# 3_0V_2_5V_DIST.net
KiCad netlist of a schematic drawn in Altium Designer
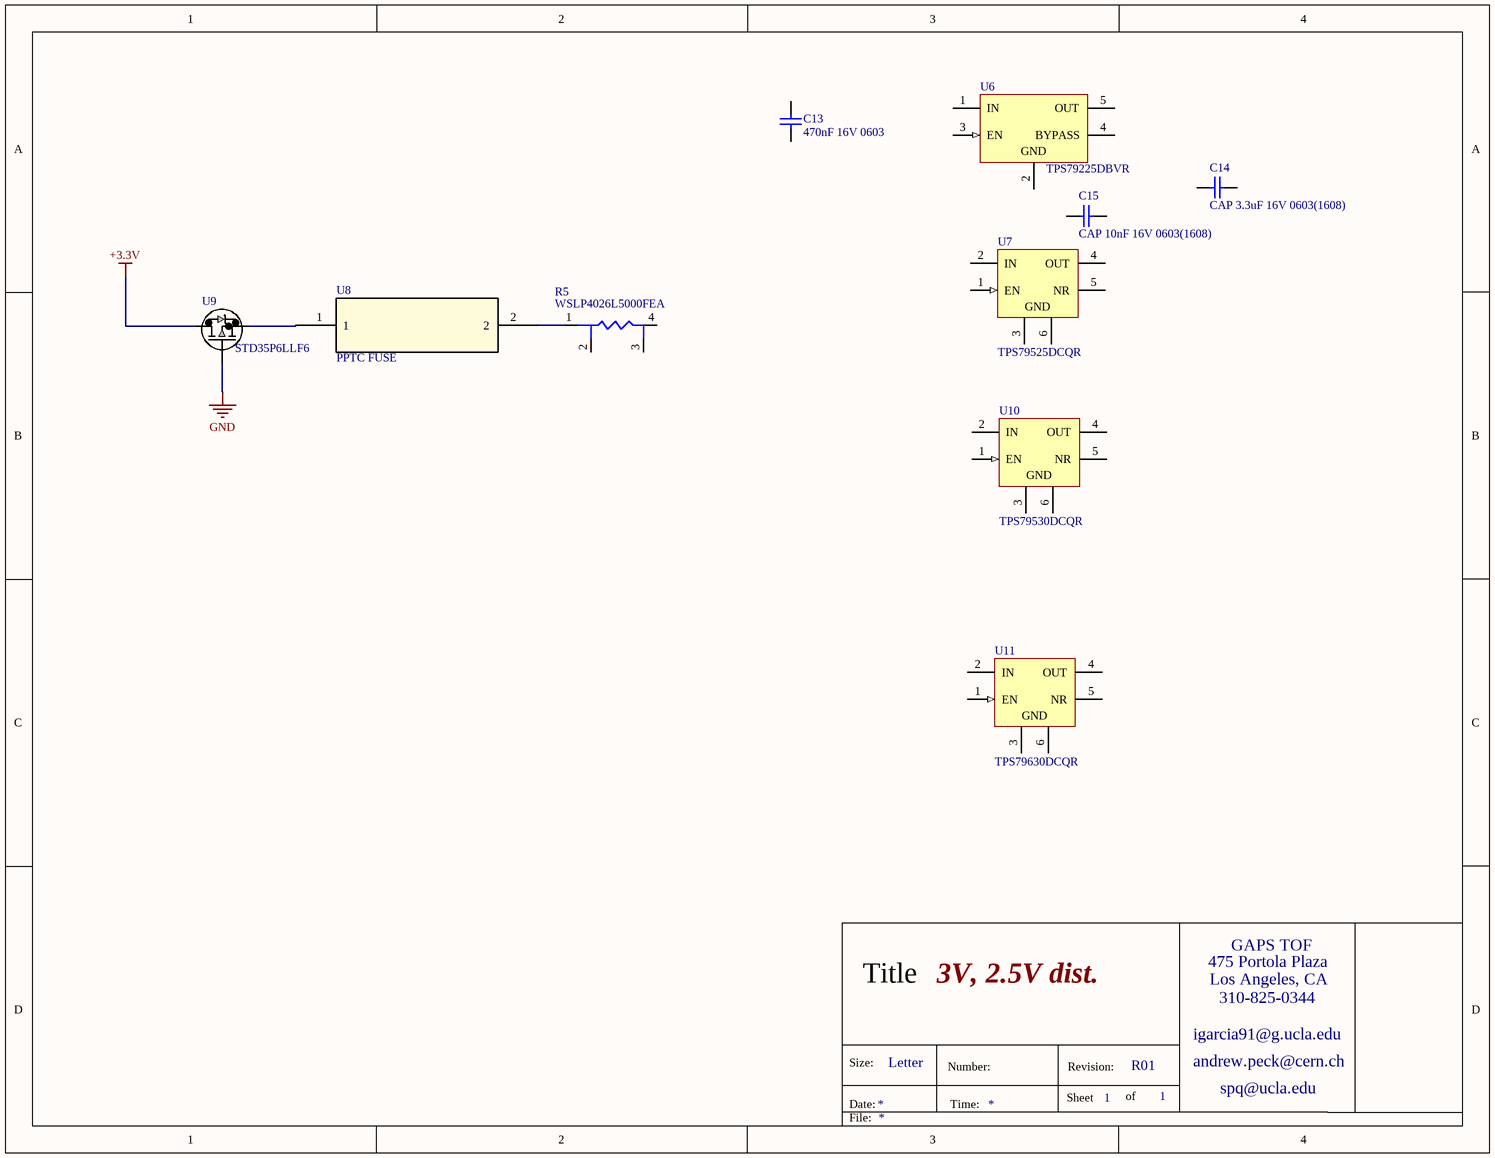
[diagram p0: 3_0V_2_5V_DIST.SchDoc]

(export (version "E")
  (design (tool "Eeschema 10.0.6"))
  (components
    (comp (ref "C13")
      (value "470nF 16V 0603")
      (footprint "CAPC0603(1608)100_M")
      (description "CAP 470nF 16V ±10% 0603 (1608 Metric) Thickness 1mm SMD")
      (fields (field (name "TOLERANCE") "Â±10%"))
      (libsource (lib "Altium Content Vault") (part "CAP"))
    )
    (comp (ref "C14")
      (value "CAP 3.3uF 16V 0603(1608)")
      (footprint "CAPC0603(1608)100_L")
      (description "CAP 3.3uF 16V ±20% 0603 (1608 Metric) Thickness 1mm SMD")
      (fields (field (name "TOLERANCE") "Â±20%"))
      (libsource (lib "Altium Content Vault") (part "CAP"))
    )
    (comp (ref "C15")
      (value "CAP 10nF 16V 0603(1608)")
      (footprint "CAPC0603(1608)100_L")
      (description "CAP 10nF 16V ±10% 0603 (1608 Metric) Thickness 1mm SMD")
      (fields (field (name "TOLERANCE") "Â±10%"))
      (libsource (lib "Altium Content Vault") (part "CAP"))
    )
    (comp (ref "R5")
      (value "WSLP4026L5000FEA")
      (description "Current Sense Resistors - SMD 7watt .0005ohm 1%")
      (libsource (lib "WSLP4026L5000FEA") (part "WSLP4026L5000FEA"))
    )
    (comp (ref "U6")
      (value "TPS79225DBVR")
      (footprint "DBV0005A_M")
      (fields (field (name "MANUFACTURER") "Texas Instruments"))
      (libsource (lib "TPS79225DBVR") (part "CMP-0394-00239-2"))
    )
    (comp (ref "U7")
      (value "TPS79525DCQR")
      (footprint "DCQ0006A_L")
      (fields (field (name "MANUFACTURER") "Texas Instruments"))
      (libsource (lib "TPS79525DCQR") (part "CMP-0395-00444-2"))
    )
    (comp (ref "U8")
      (value "PPTC FUSE")
      (footprint "0ZCF")
      (description "Resettable Fuses - PPTC")
      (fields (field (name "MANUFACTURER_PART_NUMBER") "0ZCF0250FF2C"))
      (libsource (lib "0ZCF0250FF2C") (part "0ZCF0250FF2C"))
    )
    (comp (ref "U9")
      (value "STD35P6LLF6")
      (footprint "DPAK")
      (description "MOSFET P-channel 60 V, 0.025 Ohm typ., 35 A STripFET F6 Power MOSFET in a DPAK package")
      (fields (field (name "MANUFACTURER_PART_NUMBER") "STD35NF06T4"))
      (libsource (lib "STD35P6LLF6") (part "STD35P6LLF6"))
    )
    (comp (ref "U10")
      (value "TPS79530DCQR")
      (footprint "DCQ0006A_L")
      (fields (field (name "MANUFACTURER") "Texas Instruments"))
      (libsource (lib "TPS79530DCQR") (part "CMP-0395-00302-2"))
    )
    (comp (ref "U11")
      (value "TPS79630DCQR")
      (footprint "DCQ0006A_L")
      (fields (field (name "MANUFACTURER") "Texas Instruments"))
      (libsource (lib "TPS79630DCQR") (part "CMP-0395-00336-2"))
    )
  )
  (nets
    (net (code "1") (name "+3.3V") (class "Default")
      (node (ref "U9") (pin "2") (pinfunction "D_2") (pintype "passive"))
    )
    (net (code "2") (name "GND") (class "Default")
      (node (ref "U9") (pin "1") (pinfunction "G_1") (pintype "passive"))
    )
    (net (code "3") (name "Net-(R5-Pad1)") (class "Default")
      (node (ref "R5") (pin "1") (pintype "passive"))
      (node (ref "U8") (pin "2") (pinfunction "2_2") (pintype "passive"))
    )
    (net (code "4") (name "Net-(U9-S)") (class "Default")
      (node (ref "U8") (pin "1") (pinfunction "1_1") (pintype "passive"))
      (node (ref "U9") (pin "3") (pinfunction "S_3") (pintype "passive"))
    )
    (net (code "5") (name "unconnected-(C13-Pad1)") (class "Default")
      (node (ref "C13") (pin "1") (pinfunction "1_1") (pintype "passive"))
    )
    (net (code "6") (name "unconnected-(C13-Pad2)") (class "Default")
      (node (ref "C13") (pin "2") (pinfunction "2_2") (pintype "passive"))
    )
    (net (code "7") (name "unconnected-(C14-Pad1)") (class "Default")
      (node (ref "C14") (pin "1") (pinfunction "1_1") (pintype "passive"))
    )
    (net (code "8") (name "unconnected-(C14-Pad2)") (class "Default")
      (node (ref "C14") (pin "2") (pinfunction "2_2") (pintype "passive"))
    )
    (net (code "9") (name "unconnected-(C15-Pad1)") (class "Default")
      (node (ref "C15") (pin "1") (pinfunction "1_1") (pintype "passive"))
    )
    (net (code "10") (name "unconnected-(C15-Pad2)") (class "Default")
      (node (ref "C15") (pin "2") (pinfunction "2_2") (pintype "passive"))
    )
    (net (code "11") (name "unconnected-(R5-Pad2)") (class "Default")
      (node (ref "R5") (pin "2") (pintype "passive"))
    )
    (net (code "12") (name "unconnected-(R5-Pad3)") (class "Default")
      (node (ref "R5") (pin "3") (pintype "passive"))
    )
    (net (code "13") (name "unconnected-(R5-Pad4)") (class "Default")
      (node (ref "R5") (pin "4") (pintype "passive"))
    )
    (net (code "14") (name "unconnected-(U6-BYPASS-Pad4)") (class "Default")
      (node (ref "U6") (pin "4") (pinfunction "BYPASS_4") (pintype "passive"))
    )
    (net (code "15") (name "unconnected-(U6-EN-Pad3)") (class "Default")
      (node (ref "U6") (pin "3") (pinfunction "EN_3") (pintype "input"))
    )
    (net (code "16") (name "unconnected-(U6-GND-Pad2)") (class "Default")
      (node (ref "U6") (pin "2") (pinfunction "GND_2") (pintype "power_in"))
    )
    (net (code "17") (name "unconnected-(U6-IN-Pad1)") (class "Default")
      (node (ref "U6") (pin "1") (pinfunction "IN_1") (pintype "power_in"))
    )
    (net (code "18") (name "unconnected-(U6-OUT-Pad5)") (class "Default")
      (node (ref "U6") (pin "5") (pinfunction "OUT_5") (pintype "power_in"))
    )
    (net (code "19") (name "unconnected-(U7-EN-Pad1)") (class "Default")
      (node (ref "U7") (pin "1") (pinfunction "EN_1") (pintype "input"))
    )
    (net (code "20") (name "unconnected-(U7-GND-Pad3)") (class "Default")
      (node (ref "U7") (pin "3") (pinfunction "GND_3") (pintype "power_in"))
    )
    (net (code "21") (name "unconnected-(U7-GND-Pad6)") (class "Default")
      (node (ref "U7") (pin "6") (pinfunction "GND_6") (pintype "power_in"))
    )
    (net (code "22") (name "unconnected-(U7-IN-Pad2)") (class "Default")
      (node (ref "U7") (pin "2") (pinfunction "IN_2") (pintype "power_in"))
    )
    (net (code "23") (name "unconnected-(U7-NR-Pad5)") (class "Default")
      (node (ref "U7") (pin "5") (pinfunction "NR_5") (pintype "passive"))
    )
    (net (code "24") (name "unconnected-(U7-OUT-Pad4)") (class "Default")
      (node (ref "U7") (pin "4") (pinfunction "OUT_4") (pintype "power_in"))
    )
    (net (code "25") (name "unconnected-(U10-EN-Pad1)") (class "Default")
      (node (ref "U10") (pin "1") (pinfunction "EN_1") (pintype "input"))
    )
    (net (code "26") (name "unconnected-(U10-GND-Pad3)") (class "Default")
      (node (ref "U10") (pin "3") (pinfunction "GND_3") (pintype "power_in"))
    )
    (net (code "27") (name "unconnected-(U10-GND-Pad6)") (class "Default")
      (node (ref "U10") (pin "6") (pinfunction "GND_6") (pintype "power_in"))
    )
    (net (code "28") (name "unconnected-(U10-IN-Pad2)") (class "Default")
      (node (ref "U10") (pin "2") (pinfunction "IN_2") (pintype "power_in"))
    )
    (net (code "29") (name "unconnected-(U10-NR-Pad5)") (class "Default")
      (node (ref "U10") (pin "5") (pinfunction "NR_5") (pintype "passive"))
    )
    (net (code "30") (name "unconnected-(U10-OUT-Pad4)") (class "Default")
      (node (ref "U10") (pin "4") (pinfunction "OUT_4") (pintype "power_in"))
    )
    (net (code "31") (name "unconnected-(U11-EN-Pad1)") (class "Default")
      (node (ref "U11") (pin "1") (pinfunction "EN_1") (pintype "input"))
    )
    (net (code "32") (name "unconnected-(U11-GND-Pad3)") (class "Default")
      (node (ref "U11") (pin "3") (pinfunction "GND_3") (pintype "power_in"))
    )
    (net (code "33") (name "unconnected-(U11-GND-Pad6)") (class "Default")
      (node (ref "U11") (pin "6") (pinfunction "GND_6") (pintype "power_in"))
    )
    (net (code "34") (name "unconnected-(U11-IN-Pad2)") (class "Default")
      (node (ref "U11") (pin "2") (pinfunction "IN_2") (pintype "power_in"))
    )
    (net (code "35") (name "unconnected-(U11-NR-Pad5)") (class "Default")
      (node (ref "U11") (pin "5") (pinfunction "NR_5") (pintype "passive"))
    )
    (net (code "36") (name "unconnected-(U11-OUT-Pad4)") (class "Default")
      (node (ref "U11") (pin "4") (pinfunction "OUT_4") (pintype "power_in"))
    )
  )
)
